# Supply_Swithes_2V5-1V8.net
KiCad netlist of a schematic drawn in Altium Designer
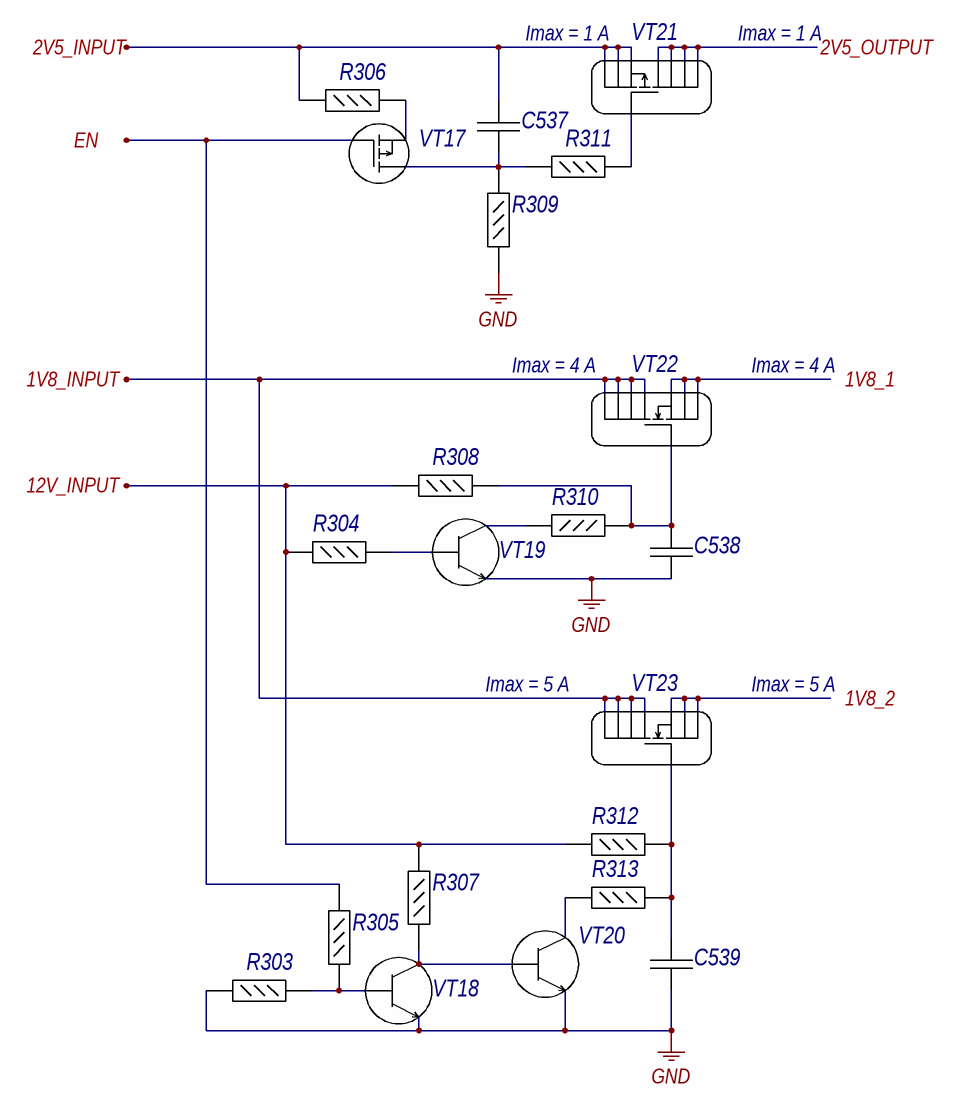
[diagram p0: Supply Swithes 2V5-1V8.SchDoc]

(export (version "E")
  (design (tool "Eeschema 10.0.6"))
  (components
    (comp (ref "C537")
      (value "CGB2A1X5R1E105K033BC")
      (footprint "CAPC1005X33X10LL5")
      (description "Chip Capacitor, 1 uF, +/- 10%, 25 V, -55 to 85 degC, 0402 (1005 Metric), RoHS, Tape and Reel")
      (fields (field (name "TOLERANCE") "10%"))
      (libsource (lib "MiniPC DB") (part "CAP_NP"))
    )
    (comp (ref "C538")
      (value "GRM155R71H103KA88D")
      (footprint "CAPC1005X55X25ML05T10")
      (description "Chip Capacitor, 10 nF, +/- 10%, 50 V, -55 to 125 degC, 0402 (1005 Metric), RoHS, Tape and Reel")
      (fields (field (name "TOLERANCE") "10%") (field (name "MANUFACTURER") "Basic Passives"))
      (libsource (lib "MiniPC DB") (part "CAP_NP"))
    )
    (comp (ref "C539")
      (value "GRM155R71H103KA88D")
      (footprint "CAPC1005X55X25ML05T10")
      (description "Chip Capacitor, 10 nF, +/- 10%, 50 V, -55 to 125 degC, 0402 (1005 Metric), RoHS, Tape and Reel")
      (fields (field (name "TOLERANCE") "10%") (field (name "MANUFACTURER") "Basic Passives"))
      (libsource (lib "MiniPC DB") (part "CAP_NP"))
    )
    (comp (ref "R303")
      (value "ERJ-2RKF1002X")
      (footprint "RESC1005X40X25LL05T05")
      (description "Chip Resistor, 10 KOhm, +/- 1%, 100 mW, -55 to 155 degC, 0402 (1005 Metric), RoHS, Tape and Reel")
      (fields (field (name "TOLERANCE") "1%") (field (name "MANUFACTURER") "Basic Passives"))
      (libsource (lib "") (part "RES-0.05_1"))
    )
    (comp (ref "R304")
      (value "ERJ-2RKF1003X")
      (footprint "RESC1005X40X25LL05T05")
      (description "Chip Resistor, 100 KOhm, +/- 1%, 100 mW, -55 to 155 degC, 0402 (1005 Metric), RoHS, Tape and Reel")
      (fields (field (name "TOLERANCE") "1%") (field (name "MANUFACTURER") "Basic Passives"))
      (libsource (lib "MiniPC DB") (part "RES-0.05"))
    )
    (comp (ref "R305")
      (value "ERJ-2RKF1002X")
      (footprint "RESC1005X40X25LL05T05")
      (description "Chip Resistor, 10 KOhm, +/- 1%, 100 mW, -55 to 155 degC, 0402 (1005 Metric), RoHS, Tape and Reel")
      (fields (field (name "TOLERANCE") "1%") (field (name "MANUFACTURER") "Basic Passives"))
      (libsource (lib "") (part "RES-0.05_2"))
    )
    (comp (ref "R306")
      (value "ERJ-2RKF10R0X")
      (footprint "RESC1005X40X25LL05T05")
      (description "Chip Resistor, 10 Ohm, +/- 1%, 100 mW, -55 to 155 degC, 0402 (1005 Metric), RoHS, Tape and Reel")
      (fields (field (name "TOLERANCE") "1%") (field (name "MANUFACTURER") "Basic Passives"))
      (libsource (lib "MiniPC DB") (part "RES-0.05"))
    )
    (comp (ref "R307")
      (value "ERJ-2RKF1003X")
      (footprint "RESC1005X40X25LL05T05")
      (description "Chip Resistor, 100 KOhm, +/- 1%, 100 mW, -55 to 155 degC, 0402 (1005 Metric), RoHS, Tape and Reel")
      (fields (field (name "TOLERANCE") "1%") (field (name "MANUFACTURER") "Basic Passives"))
      (libsource (lib "") (part "RES-0.05_2"))
    )
    (comp (ref "R308")
      (value "ERJ-2RKF1003X")
      (footprint "RESC1005X40X25LL05T05")
      (description "Chip Resistor, 100 KOhm, +/- 1%, 100 mW, -55 to 155 degC, 0402 (1005 Metric), RoHS, Tape and Reel")
      (fields (field (name "TOLERANCE") "1%") (field (name "MANUFACTURER") "Basic Passives"))
      (libsource (lib "MiniPC DB") (part "RES-0.05"))
    )
    (comp (ref "R309")
      (value "ERJ-2RKF4992X")
      (footprint "RESC1005X40X25LL05T05")
      (description "Chip Resistor, 49.9 KOhm, +/- 1%, 100 mW, -55 to 155 degC, 0402 (1005 Metric), RoHS, Tape and Reel")
      (fields (field (name "TOLERANCE") "1%") (field (name "MANUFACTURER") "Basic Passives"))
      (libsource (lib "") (part "RES-0.05_2"))
    )
    (comp (ref "R310")
      (value "ERJ-2RKF1001X")
      (footprint "RESC1005X40X25LL05T05")
      (description "Chip Resistor, 1 KOhm, +/- 1%, 100 mW, -55 to 155 degC, 0402 (1005 Metric), RoHS, Tape and Reel")
      (fields (field (name "TOLERANCE") "1%") (field (name "MANUFACTURER") "Basic Passives"))
      (libsource (lib "") (part "RES-0.05_2"))
    )
    (comp (ref "R311")
      (value "ERJ-2RKF10R0X")
      (footprint "RESC1005X40X25LL05T05")
      (description "Chip Resistor, 10 Ohm, +/- 1%, 100 mW, -55 to 155 degC, 0402 (1005 Metric), RoHS, Tape and Reel")
      (fields (field (name "TOLERANCE") "1%") (field (name "MANUFACTURER") "Basic Passives"))
      (libsource (lib "") (part "RES-0.05_1"))
    )
    (comp (ref "R312")
      (value "ERJ-2RKF1003X")
      (footprint "RESC1005X40X25LL05T05")
      (description "Chip Resistor, 100 KOhm, +/- 1%, 100 mW, -55 to 155 degC, 0402 (1005 Metric), RoHS, Tape and Reel")
      (fields (field (name "TOLERANCE") "1%") (field (name "MANUFACTURER") "Basic Passives"))
      (libsource (lib "MiniPC DB") (part "RES-0.05"))
    )
    (comp (ref "R313")
      (value "ERJ-2RKF1001X")
      (footprint "RESC1005X40X25LL05T05")
      (description "Chip Resistor, 1 KOhm, +/- 1%, 100 mW, -55 to 155 degC, 0402 (1005 Metric), RoHS, Tape and Reel")
      (fields (field (name "TOLERANCE") "1%") (field (name "MANUFACTURER") "Basic Passives"))
      (libsource (lib "") (part "RES-0.05_1"))
    )
    (comp (ref "VT17")
      (value "DMG2305UX-7")
      (footprint "DIOD-SOT23-3_A_V")
      (description "P-Channel Enhancement Mode MOSFET, 20 V, -55 to 150 degC, 3-Pin SOT23, RoHS, Tape and Reel")
      (fields (field (name "MANUFACTURER") "Diodes Inc"))
      (libsource (lib "MiniPC DB") (part "MOSFET-P-IND"))
    )
    (comp (ref "VT18")
      (value "MMBT2222A-7-F")
      (footprint "DIOD-SOT23-3_V")
      (description "NPN Small Signal Transistor, 40 V, -55 to 150 degC, 3-Pin SOT23, RoHS, Tape and Reel")
      (fields (field (name "MANUFACTURER") "Diodes Inc"))
      (libsource (lib "") (part "BJT-NPN-BEC_1"))
    )
    (comp (ref "VT19")
      (value "MMBT2222A-7-F")
      (footprint "DIOD-SOT23-3_V")
      (description "NPN Small Signal Transistor, 40 V, -55 to 150 degC, 3-Pin SOT23, RoHS, Tape and Reel")
      (fields (field (name "MANUFACTURER") "Diodes Inc"))
      (libsource (lib "MiniPC DB") (part "BJT-NPN-BEC"))
    )
    (comp (ref "VT20")
      (value "MMBT2222A-7-F")
      (footprint "DIOD-SOT23-3_V")
      (description "NPN Small Signal Transistor, 40 V, -55 to 150 degC, 3-Pin SOT23, RoHS, Tape and Reel")
      (fields (field (name "MANUFACTURER") "Diodes Inc"))
      (libsource (lib "MiniPC DB") (part "BJT-NPN-BEC"))
    )
    (comp (ref "VT21")
      (value "SiSS23DN-T1-GE3")
      (footprint "VISH-PPAK1212-8S_V")
      (description "P-Channel MOSFET, 20 V, -50 to 150 degC, 8-Pin SMD (PPAK1212-8S), RoHS, Tape and Reel")
      (libsource (lib "MiniPC DB") (part "MOSFET-P-IND_2"))
    )
    (comp (ref "VT22")
      (value "SiRA00DP-T1-GE3")
      (footprint "VISH-PPAKSO-8_V")
      (description "N-Channe MOSFET, 30 V, -55 to 150 degC, 8-Pin SMD (PPAKSO-8), RoHS, Tape and Reel")
      (libsource (lib "MiniPC DB") (part "MOSFET-N-IND_2"))
    )
    (comp (ref "VT23")
      (value "SiRA00DP-T1-GE3")
      (footprint "VISH-PPAKSO-8_V")
      (description "N-Channe MOSFET, 30 V, -55 to 150 degC, 8-Pin SMD (PPAKSO-8), RoHS, Tape and Reel")
      (libsource (lib "MiniPC DB") (part "MOSFET-N-IND_2"))
    )
  )
  (nets
    (net (code "1") (name "/1V8_1") (class "Default")
      (node (ref "VT22") (pin "1") (pinfunction "S_1") (pintype "passive"))
      (node (ref "VT22") (pin "2") (pinfunction "S_2") (pintype "passive"))
      (node (ref "VT22") (pin "3") (pinfunction "S_3") (pintype "passive"))
    )
    (net (code "2") (name "/1V8_2") (class "Default")
      (node (ref "VT23") (pin "1") (pinfunction "S_1") (pintype "passive"))
      (node (ref "VT23") (pin "2") (pinfunction "S_2") (pintype "passive"))
      (node (ref "VT23") (pin "3") (pinfunction "S_3") (pintype "passive"))
    )
    (net (code "3") (name "/1V8_INPUT") (class "Default")
      (node (ref "VT22") (pin "5") (pinfunction "D_5") (pintype "passive"))
      (node (ref "VT22") (pin "6") (pinfunction "D_6") (pintype "passive"))
      (node (ref "VT22") (pin "7") (pinfunction "D_7") (pintype "passive"))
      (node (ref "VT22") (pin "8") (pinfunction "D_8") (pintype "passive"))
      (node (ref "VT23") (pin "5") (pinfunction "D_5") (pintype "passive"))
      (node (ref "VT23") (pin "6") (pinfunction "D_6") (pintype "passive"))
      (node (ref "VT23") (pin "7") (pinfunction "D_7") (pintype "passive"))
      (node (ref "VT23") (pin "8") (pinfunction "D_8") (pintype "passive"))
    )
    (net (code "4") (name "/2V5_INPUT") (class "Default")
      (node (ref "C537") (pin "2") (pinfunction "2_2") (pintype "passive"))
      (node (ref "R306") (pin "2") (pinfunction "2_2") (pintype "passive"))
      (node (ref "VT21") (pin "1") (pinfunction "S_1") (pintype "passive"))
      (node (ref "VT21") (pin "2") (pinfunction "S_2") (pintype "passive"))
      (node (ref "VT21") (pin "3") (pinfunction "S_3") (pintype "passive"))
    )
    (net (code "5") (name "/2V5_OUTPUT") (class "Default")
      (node (ref "VT21") (pin "5") (pinfunction "D_5") (pintype "passive"))
      (node (ref "VT21") (pin "6") (pinfunction "D_6") (pintype "passive"))
      (node (ref "VT21") (pin "7") (pinfunction "D_7") (pintype "passive"))
      (node (ref "VT21") (pin "8") (pinfunction "D_8") (pintype "passive"))
    )
    (net (code "6") (name "/12V_INPUT") (class "Default")
      (node (ref "R304") (pin "2") (pinfunction "2_2") (pintype "passive"))
      (node (ref "R307") (pin "2") (pinfunction "2_2") (pintype "passive"))
      (node (ref "R308") (pin "2") (pinfunction "2_2") (pintype "passive"))
      (node (ref "R312") (pin "2") (pinfunction "2_2") (pintype "passive"))
    )
    (net (code "7") (name "/EN") (class "Default")
      (node (ref "R305") (pin "2") (pinfunction "2_2") (pintype "passive"))
      (node (ref "VT17") (pin "1") (pinfunction "1_1") (pintype "passive"))
    )
    (net (code "8") (name "GND") (class "Default")
      (node (ref "C538") (pin "1") (pinfunction "1_1") (pintype "passive"))
      (node (ref "C539") (pin "1") (pinfunction "1_1") (pintype "passive"))
      (node (ref "R303") (pin "1") (pinfunction "1_1") (pintype "passive"))
      (node (ref "R309") (pin "1") (pinfunction "1_1") (pintype "passive"))
      (node (ref "VT18") (pin "2") (pinfunction "2_2") (pintype "passive"))
      (node (ref "VT19") (pin "2") (pinfunction "2_2") (pintype "passive"))
      (node (ref "VT20") (pin "2") (pinfunction "2_2") (pintype "passive"))
    )
    (net (code "9") (name "Net-(C537-Pad1)") (class "Default")
      (node (ref "C537") (pin "1") (pinfunction "1_1") (pintype "passive"))
      (node (ref "R309") (pin "2") (pinfunction "2_2") (pintype "passive"))
      (node (ref "R311") (pin "1") (pinfunction "1_1") (pintype "passive"))
      (node (ref "VT17") (pin "3") (pinfunction "3_3") (pintype "passive"))
    )
    (net (code "10") (name "Net-(R303-Pad2)") (class "Default")
      (node (ref "R303") (pin "2") (pinfunction "2_2") (pintype "passive"))
      (node (ref "R305") (pin "1") (pinfunction "1_1") (pintype "passive"))
      (node (ref "VT18") (pin "1") (pinfunction "1_1") (pintype "passive"))
    )
    (net (code "11") (name "Net-(R304-Pad1)") (class "Default")
      (node (ref "R304") (pin "1") (pinfunction "1_1") (pintype "passive"))
      (node (ref "VT19") (pin "1") (pinfunction "1_1") (pintype "passive"))
    )
    (net (code "12") (name "Net-(R306-Pad1)") (class "Default")
      (node (ref "R306") (pin "1") (pinfunction "1_1") (pintype "passive"))
      (node (ref "VT17") (pin "2") (pinfunction "2_2") (pintype "passive"))
    )
    (net (code "13") (name "Net-(R307-Pad1)") (class "Default")
      (node (ref "R307") (pin "1") (pinfunction "1_1") (pintype "passive"))
      (node (ref "VT18") (pin "3") (pinfunction "3_3") (pintype "passive"))
      (node (ref "VT20") (pin "1") (pinfunction "1_1") (pintype "passive"))
    )
    (net (code "14") (name "Net-(R310-Pad1)") (class "Default")
      (node (ref "R310") (pin "1") (pinfunction "1_1") (pintype "passive"))
      (node (ref "VT19") (pin "3") (pinfunction "3_3") (pintype "passive"))
    )
    (net (code "15") (name "Net-(R313-Pad1)") (class "Default")
      (node (ref "R313") (pin "1") (pinfunction "1_1") (pintype "passive"))
      (node (ref "VT20") (pin "3") (pinfunction "3_3") (pintype "passive"))
    )
    (net (code "16") (name "Net-(VT21-G)") (class "Default")
      (node (ref "R311") (pin "2") (pinfunction "2_2") (pintype "passive"))
      (node (ref "VT21") (pin "4") (pinfunction "G_4") (pintype "passive"))
    )
    (net (code "17") (name "Net-(VT22-G)") (class "Default")
      (node (ref "C538") (pin "2") (pinfunction "2_2") (pintype "passive"))
      (node (ref "R308") (pin "1") (pinfunction "1_1") (pintype "passive"))
      (node (ref "R310") (pin "2") (pinfunction "2_2") (pintype "passive"))
      (node (ref "VT22") (pin "4") (pinfunction "G_4") (pintype "passive"))
    )
    (net (code "18") (name "Net-(VT23-G)") (class "Default")
      (node (ref "C539") (pin "2") (pinfunction "2_2") (pintype "passive"))
      (node (ref "R312") (pin "1") (pinfunction "1_1") (pintype "passive"))
      (node (ref "R313") (pin "2") (pinfunction "2_2") (pintype "passive"))
      (node (ref "VT23") (pin "4") (pinfunction "G_4") (pintype "passive"))
    )
  )
)
